# Rov3_-_zsilanie_cyfrowe.net
KiCad netlist of a schematic drawn in EAGLE
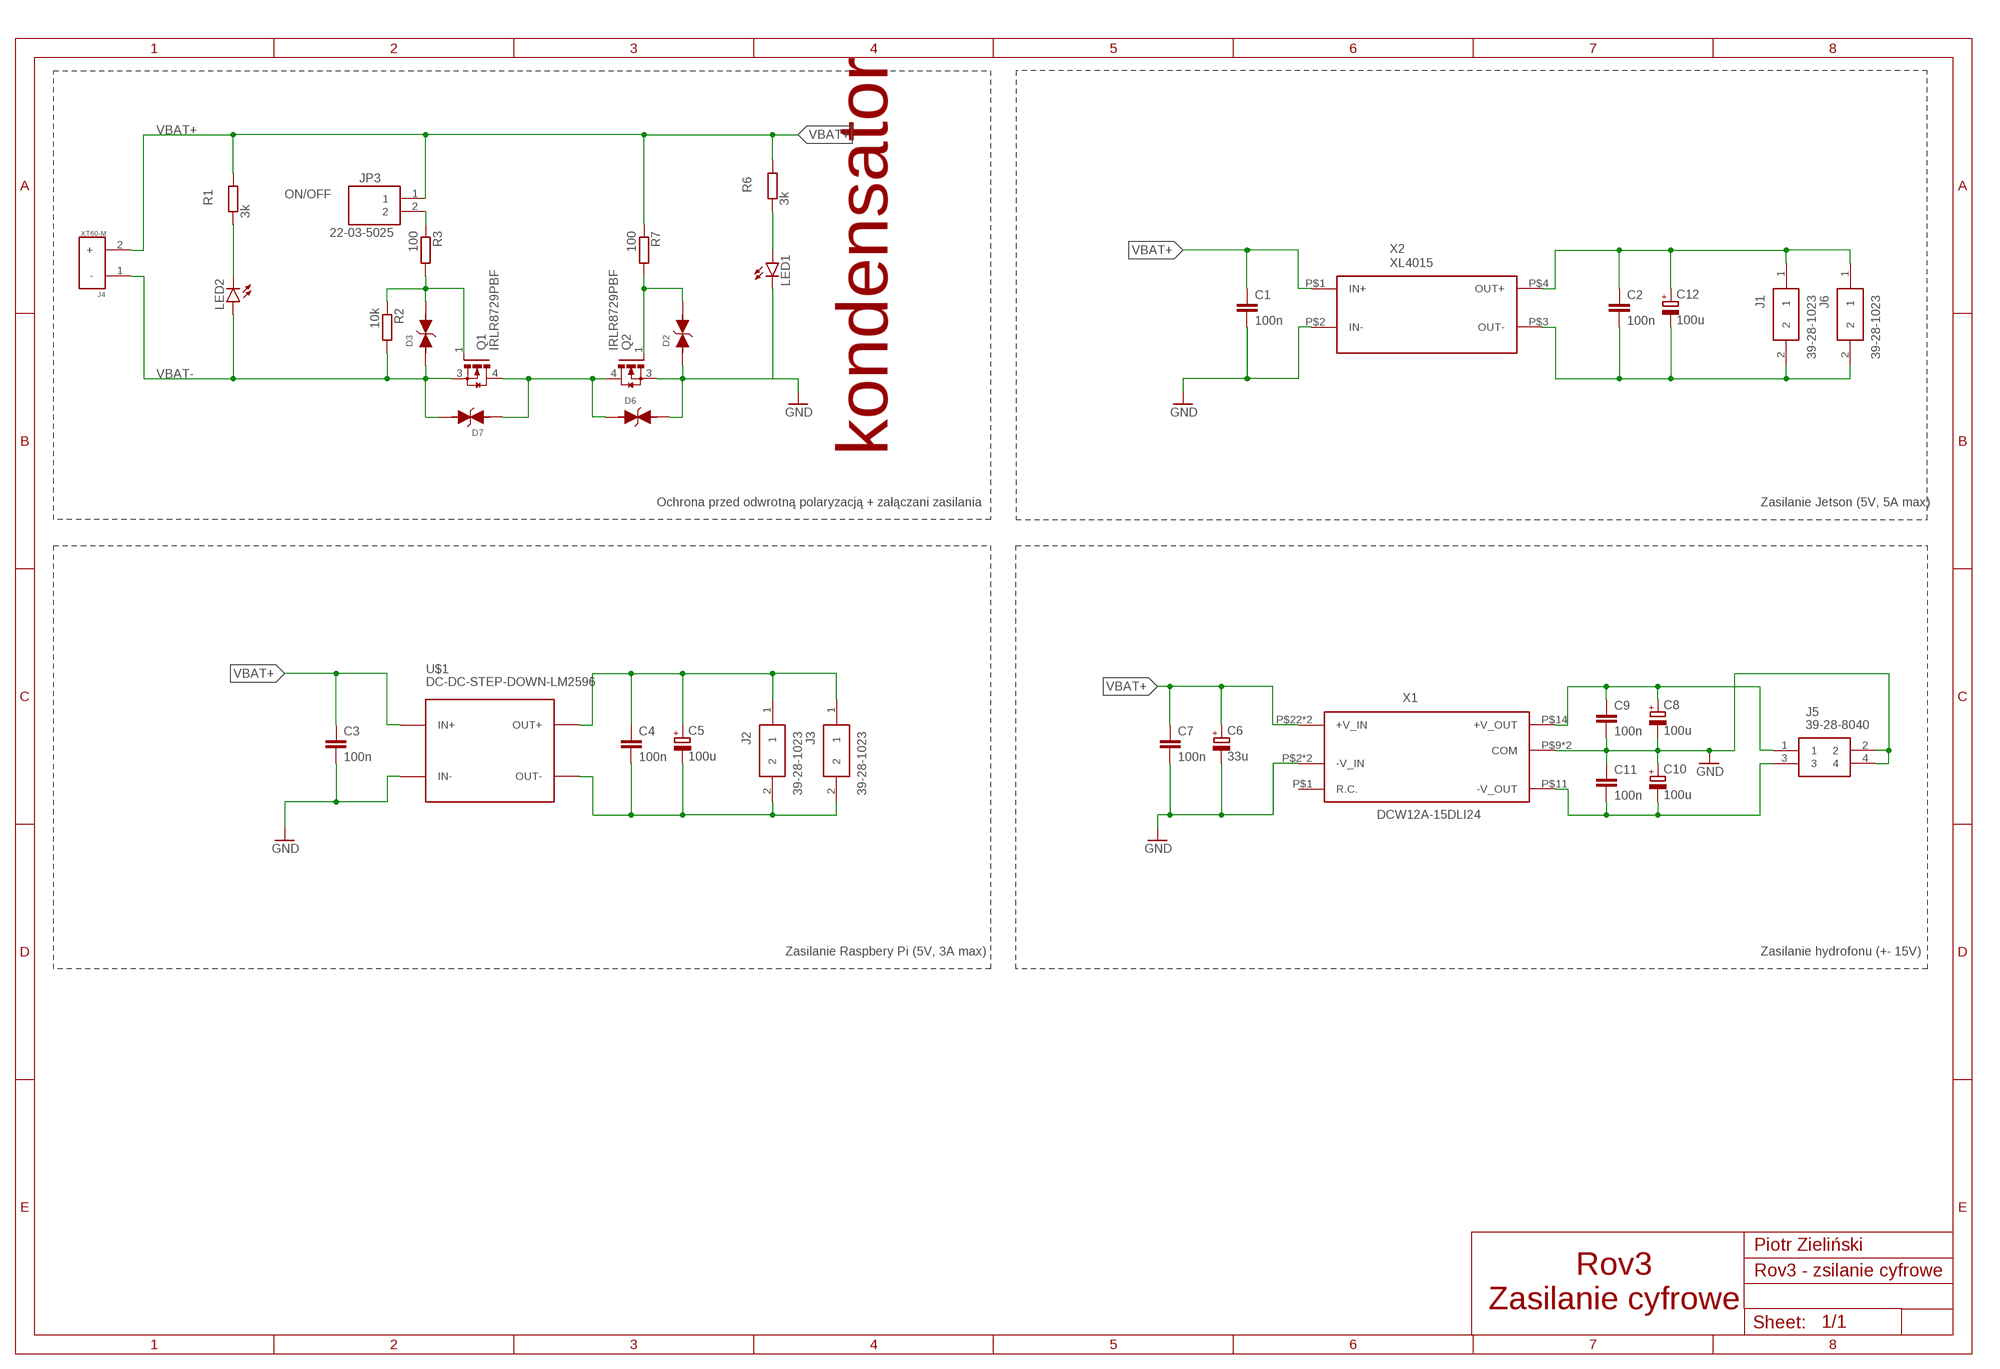
[diagram p0: schematic, sheet 1]

(export (version "E")
  (design (tool "Eeschema 10.0.6"))
  (components
    (comp (ref "C1")
      (value "100n")
      (footprint "eagle-import:C0805")
      (libsource (lib "eagle-import") (part "C-EUC0805"))
    )
    (comp (ref "C2")
      (value "100n")
      (footprint "eagle-import:C0805")
      (libsource (lib "eagle-import") (part "C-EUC0805"))
    )
    (comp (ref "C3")
      (value "100n")
      (footprint "eagle-import:C0805")
      (libsource (lib "eagle-import") (part "C-EUC0805"))
    )
    (comp (ref "C4")
      (value "100n")
      (footprint "eagle-import:C0805")
      (libsource (lib "eagle-import") (part "C-EUC0805"))
    )
    (comp (ref "C5")
      (value "100u")
      (footprint "eagle-import:E3,5-8")
      (libsource (lib "eagle-import") (part "CPOL-EUE3.5-8"))
    )
    (comp (ref "C6")
      (value "33u")
      (footprint "eagle-import:E3,5-8")
      (libsource (lib "eagle-import") (part "CPOL-EUE3.5-8"))
    )
    (comp (ref "C7")
      (value "100n")
      (footprint "eagle-import:C0805")
      (libsource (lib "eagle-import") (part "C-EUC0805"))
    )
    (comp (ref "C8")
      (value "100u")
      (footprint "eagle-import:E3,5-8")
      (libsource (lib "eagle-import") (part "CPOL-EUE3.5-8"))
    )
    (comp (ref "C9")
      (value "100n")
      (footprint "eagle-import:C0805")
      (libsource (lib "eagle-import") (part "C-EUC0805"))
    )
    (comp (ref "C10")
      (value "100u")
      (footprint "eagle-import:E3,5-8")
      (libsource (lib "eagle-import") (part "CPOL-EUE3.5-8"))
    )
    (comp (ref "C11")
      (value "100n")
      (footprint "eagle-import:C0805")
      (libsource (lib "eagle-import") (part "C-EUC0805"))
    )
    (comp (ref "C12")
      (value "100u")
      (footprint "eagle-import:E3,5-8")
      (libsource (lib "eagle-import") (part "CPOL-EUE3.5-8"))
    )
    (comp (ref "D2")
      (value "P6SMB20A_824501101")
      (footprint "eagle-import:VARTVSP_SMA_DO-214AC")
      (libsource (lib "eagle-import") (part "P6SMB20A_824501101"))
    )
    (comp (ref "D3")
      (value "P6SMB20A_824501101")
      (footprint "eagle-import:VARTVSP_SMA_DO-214AC")
      (libsource (lib "eagle-import") (part "P6SMB20A_824501101"))
    )
    (comp (ref "D6")
      (value "P6SMB20A_824501101")
      (footprint "eagle-import:VARTVSP_SMA_DO-214AC")
      (libsource (lib "eagle-import") (part "P6SMB20A_824501101"))
    )
    (comp (ref "D7")
      (value "P6SMB20A_824501101")
      (footprint "eagle-import:VARTVSP_SMA_DO-214AC")
      (libsource (lib "eagle-import") (part "P6SMB20A_824501101"))
    )
    (comp (ref "J1")
      (value "39-28-1023")
      (footprint "eagle-import:MOLEX_1X2_PCB_SOCKET")
      (fields (field (name "MOUSER_PART_NUMBER") "538-39-28-1023"))
      (libsource (lib "eagle-import") (part "39-28-1023"))
    )
    (comp (ref "J2")
      (value "39-28-1023")
      (footprint "eagle-import:MOLEX_1X2_PCB_SOCKET")
      (fields (field (name "MOUSER_PART_NUMBER") "538-39-28-1023"))
      (libsource (lib "eagle-import") (part "39-28-1023"))
    )
    (comp (ref "J3")
      (value "39-28-1023")
      (footprint "eagle-import:MOLEX_1X2_PCB_SOCKET")
      (fields (field (name "MOUSER_PART_NUMBER") "538-39-28-1023"))
      (libsource (lib "eagle-import") (part "39-28-1023"))
    )
    (comp (ref "J4")
      (value "XT60-M")
      (footprint "eagle-import:AMASS_XT60-M")
      (fields (field (name "MF") "AMASS"))
      (libsource (lib "eagle-import") (part "XT60-M"))
    )
    (comp (ref "J5")
      (value "39-28-8040")
      (footprint "eagle-import:MOLEX_2X2_PCB_SOCKET")
      (fields (field (name "MOUSER_PART_NUMBER") "538-39-28-8040"))
      (libsource (lib "eagle-import") (part "39-28-8040"))
    )
    (comp (ref "J6")
      (value "39-28-1023")
      (footprint "eagle-import:MOLEX_1X2_PCB_SOCKET")
      (fields (field (name "MOUSER_PART_NUMBER") "538-39-28-1023"))
      (libsource (lib "eagle-import") (part "39-28-1023"))
    )
    (comp (ref "JP3")
      (value "22-03-5025")
      (footprint "eagle-import:2.50MM_MINI-SPOX_2PIN_PCB_SOCKET")
      (fields (field (name "MOUSER_PART_NUMBER") "538-22-03-5025"))
      (libsource (lib "eagle-import") (part "22-03-5025"))
    )
    (comp (ref "LED1")
      (value "LEDCHIP-LED0805")
      (footprint "eagle-import:CHIP-LED0805")
      (libsource (lib "eagle-import") (part "LEDCHIP-LED0805"))
    )
    (comp (ref "LED2")
      (value "LEDCHIP-LED0805")
      (footprint "eagle-import:CHIP-LED0805")
      (libsource (lib "eagle-import") (part "LEDCHIP-LED0805"))
    )
    (comp (ref "Q1")
      (value "IRLR8729PBF")
      (footprint "eagle-import:DPAK")
      (libsource (lib "eagle-import") (part "IRLR8729PBF"))
    )
    (comp (ref "Q2")
      (value "IRLR8729PBF")
      (footprint "eagle-import:DPAK")
      (libsource (lib "eagle-import") (part "IRLR8729PBF"))
    )
    (comp (ref "R1")
      (value "3k")
      (footprint "eagle-import:R1206")
      (libsource (lib "eagle-import") (part "R-EU_R1206"))
    )
    (comp (ref "R2")
      (value "10k")
      (footprint "eagle-import:R1206")
      (libsource (lib "eagle-import") (part "R-EU_R1206"))
    )
    (comp (ref "R3")
      (value "100")
      (footprint "eagle-import:R1206")
      (libsource (lib "eagle-import") (part "R-EU_R1206"))
    )
    (comp (ref "R6")
      (value "3k")
      (footprint "eagle-import:R1206")
      (libsource (lib "eagle-import") (part "R-EU_R1206"))
    )
    (comp (ref "R7")
      (value "100")
      (footprint "eagle-import:R1206")
      (libsource (lib "eagle-import") (part "R-EU_R1206"))
    )
    (comp (ref "U$1")
      (value "DC-DC-STEP-DOWN-LM2596")
      (footprint "eagle-import:DC-DC-STEP-DOWN-LM2596")
      (libsource (lib "eagle-import") (part "DC-DC-STEP-DOWN-LM2596"))
    )
    (comp (ref "X1")
      (value "DCW12A-15DLI24")
      (footprint "eagle-import:DCW12A-15")
      (libsource (lib "eagle-import") (part "DCW12A-15DLI24"))
    )
    (comp (ref "X2")
      (value "XL4015")
      (footprint "eagle-import:XL4015")
      (libsource (lib "eagle-import") (part "XL4015"))
    )
  )
  (nets
    (net (code "1") (name "/VBAT-") (class "Default")
      (node (ref "D3") (pin "1") (pinfunction "1_1") (pintype "passive"))
      (node (ref "D7") (pin "2") (pinfunction "2_2") (pintype "passive"))
      (node (ref "J4") (pin "1") (pinfunction "-_1") (pintype "passive"))
      (node (ref "LED2") (pin "A") (pinfunction "A_A") (pintype "passive"))
      (node (ref "Q1") (pin "3") (pinfunction "S_3") (pintype "passive"))
      (node (ref "R2") (pin "2") (pinfunction "2_2") (pintype "passive"))
    )
    (net (code "2") (name "GND") (class "Default")
      (node (ref "C1") (pin "2") (pinfunction "2_2") (pintype "passive"))
      (node (ref "C10") (pin "+") (pinfunction "+_+") (pintype "passive"))
      (node (ref "C11") (pin "1") (pinfunction "1_1") (pintype "passive"))
      (node (ref "C3") (pin "2") (pinfunction "2_2") (pintype "passive"))
      (node (ref "C6") (pin "-") (pinfunction "-_-") (pintype "passive"))
      (node (ref "C7") (pin "2") (pinfunction "2_2") (pintype "passive"))
      (node (ref "C8") (pin "-") (pinfunction "-_-") (pintype "passive"))
      (node (ref "C9") (pin "2") (pinfunction "2_2") (pintype "passive"))
      (node (ref "D2") (pin "1") (pinfunction "1_1") (pintype "passive"))
      (node (ref "D6") (pin "2") (pinfunction "2_2") (pintype "passive"))
      (node (ref "J5") (pin "2") (pinfunction "2_2") (pintype "bidirectional"))
      (node (ref "J5") (pin "4") (pinfunction "4_4") (pintype "bidirectional"))
      (node (ref "LED1") (pin "C") (pinfunction "C_C") (pintype "passive"))
      (node (ref "Q2") (pin "3") (pinfunction "S_3") (pintype "passive"))
      (node (ref "U$1") (pin "IN-") (pinfunction "IN-_IN-") (pintype "bidirectional"))
      (node (ref "X1") (pin "P$16") (pinfunction "COM_P$16") (pintype "bidirectional"))
      (node (ref "X1") (pin "P$2") (pinfunction "-V_IN_P$2") (pintype "bidirectional"))
      (node (ref "X1") (pin "P$3") (pinfunction "-V_IN_P$3") (pintype "bidirectional"))
      (node (ref "X1") (pin "P$9") (pinfunction "COM_P$9") (pintype "bidirectional"))
      (node (ref "X2") (pin "P$2") (pinfunction "IN-_P$2") (pintype "bidirectional"))
    )
    (net (code "3") (name "Net-(C4-Pad1)") (class "Default")
      (node (ref "C4") (pin "1") (pinfunction "1_1") (pintype "passive"))
      (node (ref "C5") (pin "+") (pinfunction "+_+") (pintype "passive"))
      (node (ref "J2") (pin "1") (pinfunction "1_1") (pintype "bidirectional"))
      (node (ref "J3") (pin "1") (pinfunction "1_1") (pintype "bidirectional"))
      (node (ref "U$1") (pin "OUT+") (pinfunction "OUT+_OUT+") (pintype "bidirectional"))
    )
    (net (code "4") (name "Net-(C4-Pad2)") (class "Default")
      (node (ref "C4") (pin "2") (pinfunction "2_2") (pintype "passive"))
      (node (ref "C5") (pin "-") (pinfunction "-_-") (pintype "passive"))
      (node (ref "J2") (pin "2") (pinfunction "2_2") (pintype "bidirectional"))
      (node (ref "J3") (pin "2") (pinfunction "2_2") (pintype "bidirectional"))
      (node (ref "U$1") (pin "OUT-") (pinfunction "OUT-_OUT-") (pintype "bidirectional"))
    )
    (net (code "5") (name "Net-(JP3-Pad2)") (class "Default")
      (node (ref "JP3") (pin "2") (pinfunction "2_2") (pintype "bidirectional"))
      (node (ref "R3") (pin "1") (pinfunction "1_1") (pintype "passive"))
    )
    (net (code "6") (name "Net-(LED1-PadA)") (class "Default")
      (node (ref "LED1") (pin "A") (pinfunction "A_A") (pintype "passive"))
      (node (ref "R6") (pin "1") (pinfunction "1_1") (pintype "passive"))
    )
    (net (code "7") (name "Net-(LED2-PadC)") (class "Default")
      (node (ref "LED2") (pin "C") (pinfunction "C_C") (pintype "passive"))
      (node (ref "R1") (pin "1") (pinfunction "1_1") (pintype "passive"))
    )
    (net (code "8") (name "Net-(Q1-D)") (class "Default")
      (node (ref "D6") (pin "1") (pinfunction "1_1") (pintype "passive"))
      (node (ref "D7") (pin "1") (pinfunction "1_1") (pintype "passive"))
      (node (ref "Q1") (pin "4") (pinfunction "D_4") (pintype "passive"))
      (node (ref "Q2") (pin "4") (pinfunction "D_4") (pintype "passive"))
    )
    (net (code "9") (name "Net-(Q1-G)") (class "Default")
      (node (ref "D3") (pin "2") (pinfunction "2_2") (pintype "passive"))
      (node (ref "Q1") (pin "1") (pinfunction "G_1") (pintype "passive"))
      (node (ref "R2") (pin "1") (pinfunction "1_1") (pintype "passive"))
      (node (ref "R3") (pin "2") (pinfunction "2_2") (pintype "passive"))
    )
    (net (code "10") (name "Net-(Q2-G)") (class "Default")
      (node (ref "D2") (pin "2") (pinfunction "2_2") (pintype "passive"))
      (node (ref "Q2") (pin "1") (pinfunction "G_1") (pintype "passive"))
      (node (ref "R7") (pin "2") (pinfunction "2_2") (pintype "passive"))
    )
    (net (code "11") (name "Net-(X1-+V_OUT)") (class "Default")
      (node (ref "C8") (pin "+") (pinfunction "+_+") (pintype "passive"))
      (node (ref "C9") (pin "1") (pinfunction "1_1") (pintype "passive"))
      (node (ref "J5") (pin "1") (pinfunction "1_1") (pintype "bidirectional"))
      (node (ref "X1") (pin "P$14") (pinfunction "+V_OUT_P$14") (pintype "bidirectional"))
    )
    (net (code "12") (name "Net-(X1--V_OUT)") (class "Default")
      (node (ref "C10") (pin "-") (pinfunction "-_-") (pintype "passive"))
      (node (ref "C11") (pin "2") (pinfunction "2_2") (pintype "passive"))
      (node (ref "J5") (pin "3") (pinfunction "3_3") (pintype "bidirectional"))
      (node (ref "X1") (pin "P$11") (pinfunction "-V_OUT_P$11") (pintype "bidirectional"))
    )
    (net (code "13") (name "Net-(X2-OUT+)") (class "Default")
      (node (ref "C12") (pin "+") (pinfunction "+_+") (pintype "passive"))
      (node (ref "C2") (pin "1") (pinfunction "1_1") (pintype "passive"))
      (node (ref "J1") (pin "1") (pinfunction "1_1") (pintype "bidirectional"))
      (node (ref "J6") (pin "1") (pinfunction "1_1") (pintype "bidirectional"))
      (node (ref "X2") (pin "P$4") (pinfunction "OUT+_P$4") (pintype "bidirectional"))
    )
    (net (code "14") (name "Net-(X2-OUT-)") (class "Default")
      (node (ref "C12") (pin "-") (pinfunction "-_-") (pintype "passive"))
      (node (ref "C2") (pin "2") (pinfunction "2_2") (pintype "passive"))
      (node (ref "J1") (pin "2") (pinfunction "2_2") (pintype "bidirectional"))
      (node (ref "J6") (pin "2") (pinfunction "2_2") (pintype "bidirectional"))
      (node (ref "X2") (pin "P$3") (pinfunction "OUT-_P$3") (pintype "bidirectional"))
    )
    (net (code "15") (name "VBAT+") (class "Default")
      (node (ref "C1") (pin "1") (pinfunction "1_1") (pintype "passive"))
      (node (ref "C3") (pin "1") (pinfunction "1_1") (pintype "passive"))
      (node (ref "C6") (pin "+") (pinfunction "+_+") (pintype "passive"))
      (node (ref "C7") (pin "1") (pinfunction "1_1") (pintype "passive"))
      (node (ref "J4") (pin "2") (pinfunction "+_2") (pintype "passive"))
      (node (ref "JP3") (pin "1") (pinfunction "1_1") (pintype "bidirectional"))
      (node (ref "R1") (pin "2") (pinfunction "2_2") (pintype "passive"))
      (node (ref "R6") (pin "2") (pinfunction "2_2") (pintype "passive"))
      (node (ref "R7") (pin "1") (pinfunction "1_1") (pintype "passive"))
      (node (ref "U$1") (pin "IN+") (pinfunction "IN+_IN+") (pintype "bidirectional"))
      (node (ref "X1") (pin "P$22") (pinfunction "+V_IN_P$22") (pintype "bidirectional"))
      (node (ref "X1") (pin "P$23") (pinfunction "+V_IN_P$23") (pintype "bidirectional"))
      (node (ref "X2") (pin "P$1") (pinfunction "IN+_P$1") (pintype "bidirectional"))
    )
    (net (code "16") (name "unconnected-(X1-R.C.-PadP$1)") (class "Default")
      (node (ref "X1") (pin "P$1") (pinfunction "R.C._P$1") (pintype "bidirectional"))
    )
  )
)
